# imwiser-esp-v01.net
KiCad netlist of a schematic drawn in EAGLE
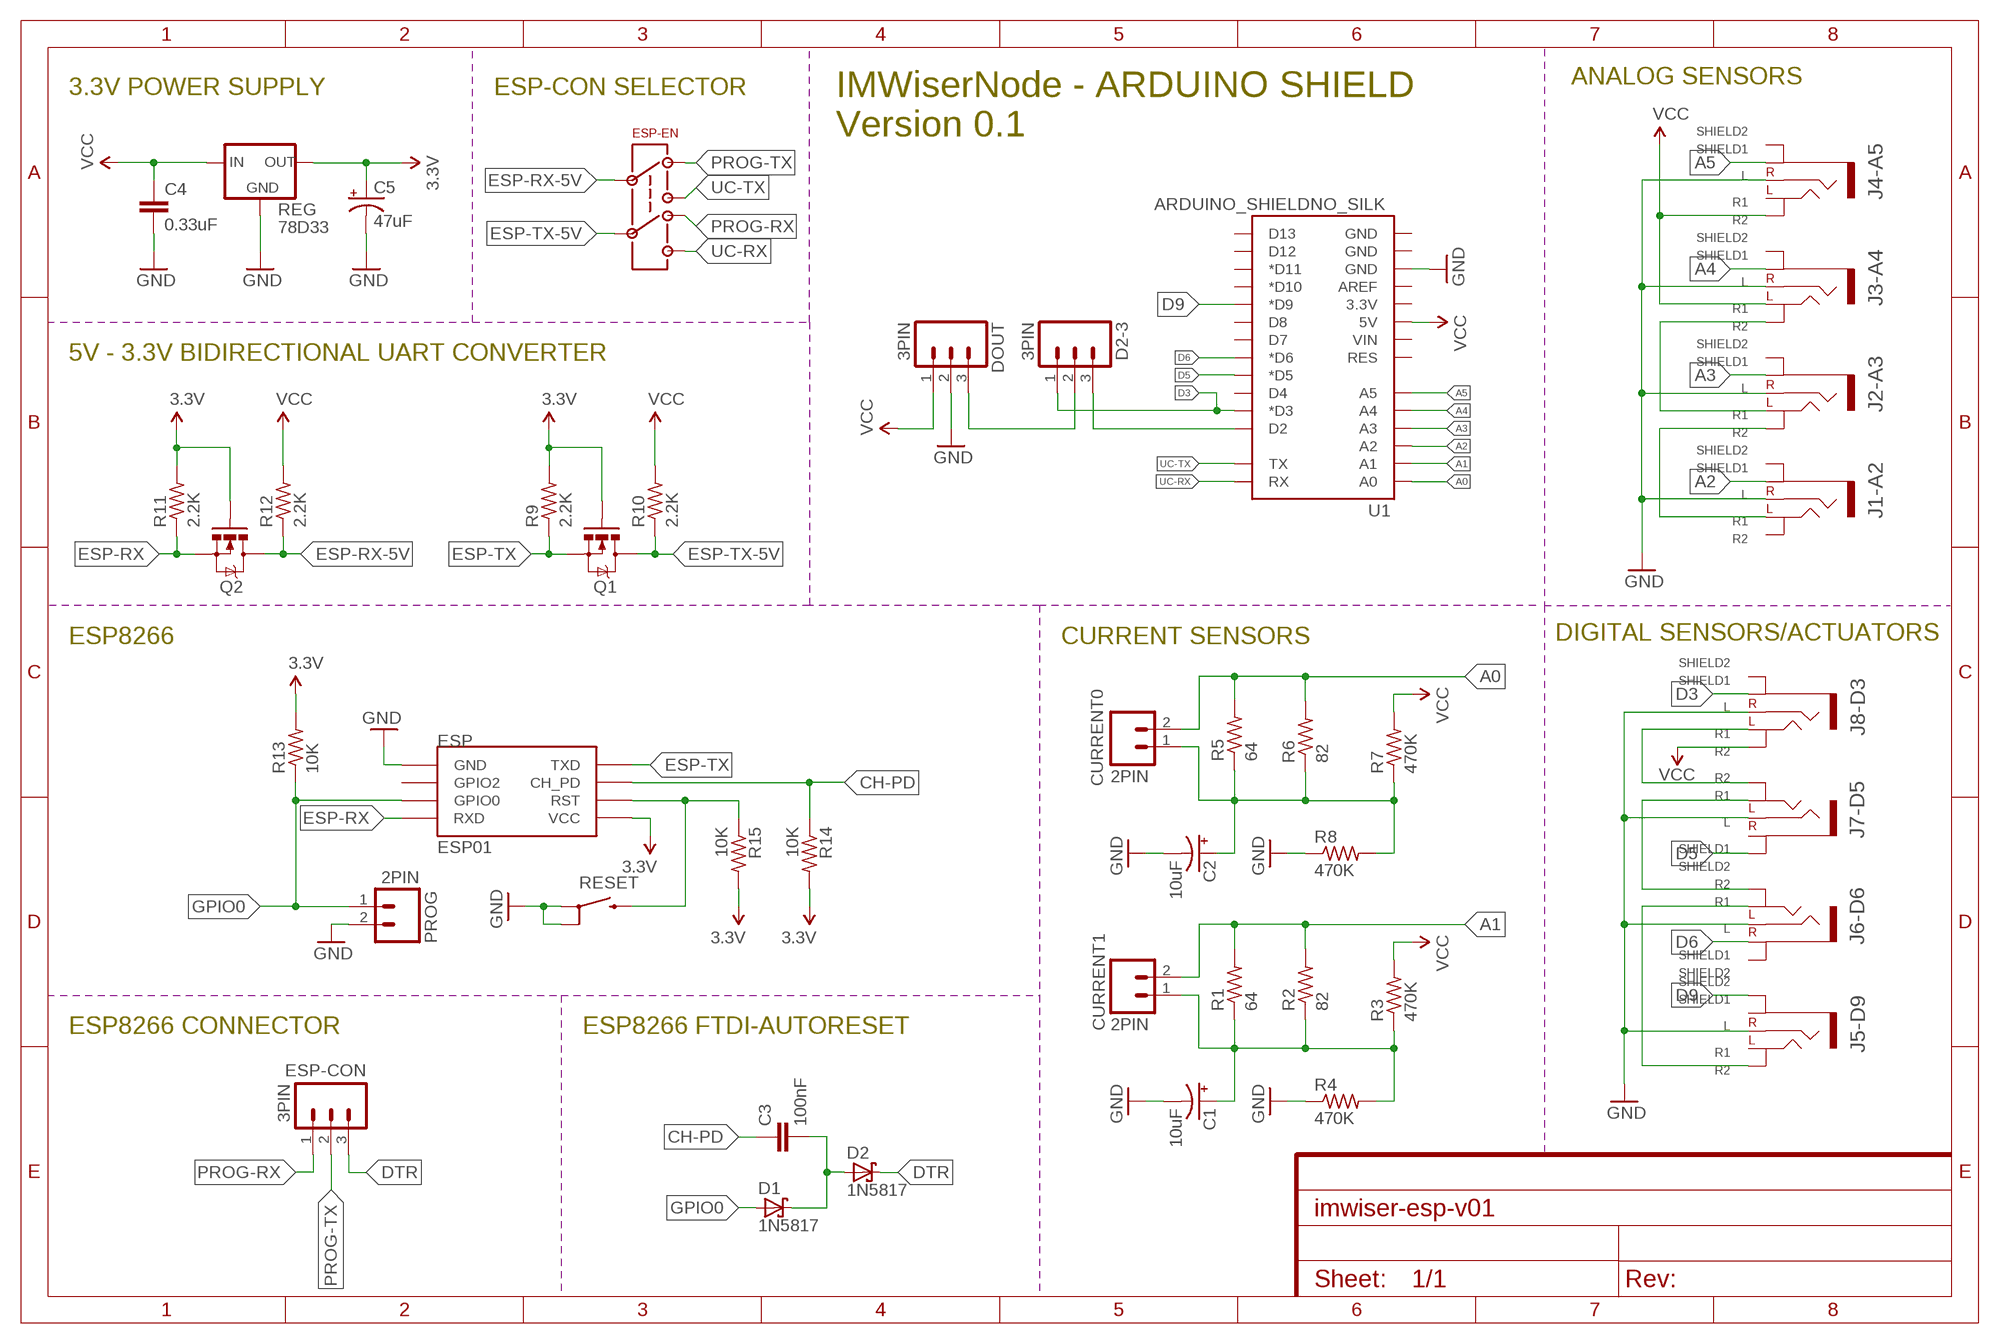
[diagram p0: schematic, sheet 1]

(export (version "E")
  (design (tool "Eeschema 10.0.6"))
  (components
    (comp (ref "C1")
      (value "10uF")
      (footprint "eagle-import:CPOL-RADIAL-10UF-25V")
      (libsource (lib "eagle-import") (part "10UF-25V-20%(PTH)"))
    )
    (comp (ref "C2")
      (value "10uF")
      (footprint "eagle-import:CPOL-RADIAL-10UF-25V")
      (libsource (lib "eagle-import") (part "10UF-25V-20%(PTH)"))
    )
    (comp (ref "C3")
      (value "100nF")
      (footprint "eagle-import:CAP-PTH-SMALL")
      (libsource (lib "eagle-import") (part "CAPPTH"))
    )
    (comp (ref "C4")
      (value "0.33uF")
      (footprint "eagle-import:CAP-PTH-SMALL")
      (libsource (lib "eagle-import") (part "CAPPTH"))
    )
    (comp (ref "C5")
      (value "47uF")
      (footprint "eagle-import:CPOL-RADIAL-10UF-25V")
      (libsource (lib "eagle-import") (part "10UF-25V-20%(PTH)"))
    )
    (comp (ref "CURRENT0")
      (value "2PIN")
      (footprint "eagle-import:1X02")
      (libsource (lib "eagle-import") (part "M02PTH"))
    )
    (comp (ref "CURRENT1")
      (value "2PIN")
      (footprint "eagle-import:1X02")
      (libsource (lib "eagle-import") (part "M02PTH"))
    )
    (comp (ref "D1")
      (value "1N5817")
      (footprint "eagle-import:DO41-7")
      (libsource (lib "eagle-import") (part "SCHOTTKY-DIODEDO41-7"))
    )
    (comp (ref "D2")
      (value "1N5817")
      (footprint "eagle-import:DO41-7")
      (libsource (lib "eagle-import") (part "SCHOTTKY-DIODEDO41-7"))
    )
    (comp (ref "D2-3")
      (value "3PIN")
      (footprint "eagle-import:1X03")
      (libsource (lib "eagle-import") (part "M03PTH"))
    )
    (comp (ref "DOUT")
      (value "3PIN")
      (footprint "eagle-import:1X03")
      (libsource (lib "eagle-import") (part "M03PTH"))
    )
    (comp (ref "ESP")
      (value "ESP01")
      (footprint "eagle-import:ESP01")
      (libsource (lib "eagle-import") (part "ESP01"))
    )
    (comp (ref "ESP-CON")
      (value "3PIN")
      (footprint "eagle-import:1X03")
      (libsource (lib "eagle-import") (part "M03PTH"))
    )
    (comp (ref "ESP-EN")
      (value "DPDT-GENERIC-SWITCH-7X7MM")
      (footprint "eagle-import:DPDT-PTH-7_7MM")
      (libsource (lib "eagle-import") (part "DPDT-GENERIC-SWITCH-7X7MM"))
    )
    (comp (ref "J1-A2")
      (value "PJ-313-SPAD")
      (footprint "eagle-import:PJ-313-5PIN-SMALL")
      (libsource (lib "eagle-import") (part "PJ-313-SPAD"))
    )
    (comp (ref "J2-A3")
      (value "PJ-313-SPAD")
      (footprint "eagle-import:PJ-313-5PIN-SMALL")
      (libsource (lib "eagle-import") (part "PJ-313-SPAD"))
    )
    (comp (ref "J3-A4")
      (value "PJ-313-SPAD")
      (footprint "eagle-import:PJ-313-5PIN-SMALL")
      (libsource (lib "eagle-import") (part "PJ-313-SPAD"))
    )
    (comp (ref "J4-A5")
      (value "PJ-313-SPAD")
      (footprint "eagle-import:PJ-313-5PIN-SMALL")
      (libsource (lib "eagle-import") (part "PJ-313-SPAD"))
    )
    (comp (ref "J5-D9")
      (value "PJ-313-SPAD")
      (footprint "eagle-import:PJ-313-5PIN-SMALL")
      (libsource (lib "eagle-import") (part "PJ-313-SPAD"))
    )
    (comp (ref "J6-D6")
      (value "PJ-313-SPAD")
      (footprint "eagle-import:PJ-313-5PIN-SMALL")
      (libsource (lib "eagle-import") (part "PJ-313-SPAD"))
    )
    (comp (ref "J7-D5")
      (value "PJ-313-SPAD")
      (footprint "eagle-import:PJ-313-5PIN-SMALL")
      (libsource (lib "eagle-import") (part "PJ-313-SPAD"))
    )
    (comp (ref "J8-D3")
      (value "PJ-313-SPAD")
      (footprint "eagle-import:PJ-313-5PIN-SMALL")
      (libsource (lib "eagle-import") (part "PJ-313-SPAD"))
    )
    (comp (ref "PROG")
      (value "2PIN")
      (footprint "eagle-import:1X02")
      (libsource (lib "eagle-import") (part "M02PTH"))
    )
    (comp (ref "Q1")
      (value "MOSFET-NCHANNEL2N7000")
      (footprint "eagle-import:TO-92")
      (libsource (lib "eagle-import") (part "MOSFET-NCHANNEL2N7000"))
    )
    (comp (ref "Q2")
      (value "MOSFET-NCHANNEL2N7000")
      (footprint "eagle-import:TO-92")
      (libsource (lib "eagle-import") (part "MOSFET-NCHANNEL2N7000"))
    )
    (comp (ref "R1")
      (value "64")
      (footprint "eagle-import:0207_10")
      (libsource (lib "eagle-import") (part "R-US_0207/10"))
    )
    (comp (ref "R2")
      (value "82")
      (footprint "eagle-import:0207_10")
      (libsource (lib "eagle-import") (part "R-US_0207/10"))
    )
    (comp (ref "R3")
      (value "470K")
      (footprint "eagle-import:0207_10")
      (libsource (lib "eagle-import") (part "R-US_0207/10"))
    )
    (comp (ref "R4")
      (value "470K")
      (footprint "eagle-import:0207_10")
      (libsource (lib "eagle-import") (part "R-US_0207/10"))
    )
    (comp (ref "R5")
      (value "64")
      (footprint "eagle-import:0207_10")
      (libsource (lib "eagle-import") (part "R-US_0207/10"))
    )
    (comp (ref "R6")
      (value "82")
      (footprint "eagle-import:0207_10")
      (libsource (lib "eagle-import") (part "R-US_0207/10"))
    )
    (comp (ref "R7")
      (value "470K")
      (footprint "eagle-import:0207_10")
      (libsource (lib "eagle-import") (part "R-US_0207/10"))
    )
    (comp (ref "R8")
      (value "470K")
      (footprint "eagle-import:0207_10")
      (libsource (lib "eagle-import") (part "R-US_0207/10"))
    )
    (comp (ref "R9")
      (value "2.2K")
      (footprint "eagle-import:0207_10")
      (libsource (lib "eagle-import") (part "R-US_0207/10"))
    )
    (comp (ref "R10")
      (value "2.2K")
      (footprint "eagle-import:0207_10")
      (libsource (lib "eagle-import") (part "R-US_0207/10"))
    )
    (comp (ref "R11")
      (value "2.2K")
      (footprint "eagle-import:0207_10")
      (libsource (lib "eagle-import") (part "R-US_0207/10"))
    )
    (comp (ref "R12")
      (value "2.2K")
      (footprint "eagle-import:0207_10")
      (libsource (lib "eagle-import") (part "R-US_0207/10"))
    )
    (comp (ref "R13")
      (value "10K")
      (footprint "eagle-import:0207_10")
      (libsource (lib "eagle-import") (part "R-US_0207/10"))
    )
    (comp (ref "R14")
      (value "10K")
      (footprint "eagle-import:0207_10")
      (libsource (lib "eagle-import") (part "R-US_0207/10"))
    )
    (comp (ref "R15")
      (value "10K")
      (footprint "eagle-import:0207_10")
      (libsource (lib "eagle-import") (part "R-US_0207/10"))
    )
    (comp (ref "REG")
      (value "78D33")
      (footprint "eagle-import:TO220-IGO")
      (libsource (lib "eagle-import") (part "V_REG_78XXSINK"))
    )
    (comp (ref "RESET")
      (value "SWITCH-MOMENTARY-2PTH")
      (footprint "eagle-import:TACTILE-PTH")
      (libsource (lib "eagle-import") (part "SWITCH-MOMENTARY-2PTH"))
    )
    (comp (ref "U1")
      (value "ARDUINO_SHIELDNO_SILK")
      (footprint "eagle-import:DUEMILANOVE_VIAS")
      (libsource (lib "eagle-import") (part "ARDUINO_SHIELDNO_SILK"))
    )
  )
  (nets
    (net (code "1") (name "3.3V") (class "Default")
      (node (ref "C5") (pin "1") (pinfunction "+_1") (pintype "passive"))
      (node (ref "ESP") (pin "VCC") (pinfunction "VCC_VCC") (pintype "bidirectional"))
      (node (ref "Q1") (pin "2") (pinfunction "G_2") (pintype "passive"))
      (node (ref "Q2") (pin "2") (pinfunction "G_2") (pintype "passive"))
      (node (ref "R11") (pin "2") (pinfunction "2_2") (pintype "passive"))
      (node (ref "R13") (pin "2") (pinfunction "2_2") (pintype "passive"))
      (node (ref "R14") (pin "2") (pinfunction "2_2") (pintype "passive"))
      (node (ref "R15") (pin "2") (pinfunction "2_2") (pintype "passive"))
      (node (ref "R9") (pin "2") (pinfunction "2_2") (pintype "passive"))
      (node (ref "REG") (pin "OUT") (pinfunction "OUT_OUT") (pintype "passive"))
    )
    (net (code "2") (name "A0") (class "Default")
      (node (ref "CURRENT0") (pin "2") (pinfunction "2_2") (pintype "passive"))
      (node (ref "R5") (pin "2") (pinfunction "2_2") (pintype "passive"))
      (node (ref "R6") (pin "2") (pinfunction "2_2") (pintype "passive"))
      (node (ref "U1") (pin "A0") (pinfunction "A0_A0") (pintype "bidirectional"))
    )
    (net (code "3") (name "A1") (class "Default")
      (node (ref "CURRENT1") (pin "2") (pinfunction "2_2") (pintype "passive"))
      (node (ref "R1") (pin "2") (pinfunction "2_2") (pintype "passive"))
      (node (ref "R2") (pin "2") (pinfunction "2_2") (pintype "passive"))
      (node (ref "U1") (pin "A1") (pinfunction "A1_A1") (pintype "bidirectional"))
    )
    (net (code "4") (name "A2") (class "Default")
      (node (ref "J1-A2") (pin "1.1") (pinfunction "SHIELD1_1.1") (pintype "bidirectional"))
      (node (ref "U1") (pin "A2") (pinfunction "A2_A2") (pintype "bidirectional"))
    )
    (net (code "5") (name "A3") (class "Default")
      (node (ref "J2-A3") (pin "1.1") (pinfunction "SHIELD1_1.1") (pintype "bidirectional"))
      (node (ref "U1") (pin "A3") (pinfunction "A3_A3") (pintype "bidirectional"))
    )
    (net (code "6") (name "A4") (class "Default")
      (node (ref "J3-A4") (pin "1.1") (pinfunction "SHIELD1_1.1") (pintype "bidirectional"))
      (node (ref "U1") (pin "A4") (pinfunction "A4_A4") (pintype "bidirectional"))
    )
    (net (code "7") (name "A5") (class "Default")
      (node (ref "J4-A5") (pin "1.1") (pinfunction "SHIELD1_1.1") (pintype "bidirectional"))
      (node (ref "U1") (pin "A5") (pinfunction "A5_A5") (pintype "bidirectional"))
    )
    (net (code "8") (name "CH-PD") (class "Default")
      (node (ref "C3") (pin "1") (pinfunction "1_1") (pintype "passive"))
      (node (ref "ESP") (pin "CH_PD") (pinfunction "CH_PD_CH_PD") (pintype "bidirectional"))
      (node (ref "R14") (pin "1") (pinfunction "1_1") (pintype "passive"))
    )
    (net (code "9") (name "D3") (class "Default")
      (node (ref "D2-3") (pin "1") (pinfunction "1_1") (pintype "passive"))
      (node (ref "J8-D3") (pin "1.1") (pinfunction "SHIELD1_1.1") (pintype "bidirectional"))
      (node (ref "U1") (pin "D3") (pinfunction "*D3_D3") (pintype "bidirectional"))
    )
    (net (code "10") (name "D5") (class "Default")
      (node (ref "J7-D5") (pin "1.2") (pinfunction "SHIELD2_1.2") (pintype "bidirectional"))
      (node (ref "U1") (pin "D5") (pinfunction "*D5_D5") (pintype "bidirectional"))
    )
    (net (code "11") (name "D6") (class "Default")
      (node (ref "J6-D6") (pin "1.1") (pinfunction "SHIELD1_1.1") (pintype "bidirectional"))
      (node (ref "U1") (pin "D6") (pinfunction "*D6_D6") (pintype "bidirectional"))
    )
    (net (code "12") (name "D9") (class "Default")
      (node (ref "J5-D9") (pin "1.2") (pinfunction "SHIELD2_1.2") (pintype "bidirectional"))
      (node (ref "U1") (pin "D9") (pinfunction "*D9_D9") (pintype "bidirectional"))
    )
    (net (code "13") (name "DTR") (class "Default")
      (node (ref "D2") (pin "C") (pinfunction "C_C") (pintype "passive"))
      (node (ref "ESP-CON") (pin "3") (pinfunction "3_3") (pintype "passive"))
    )
    (net (code "14") (name "ESP-RX") (class "Default")
      (node (ref "ESP") (pin "RX") (pinfunction "RXD_RX") (pintype "bidirectional"))
      (node (ref "Q2") (pin "1") (pinfunction "S_1") (pintype "passive"))
      (node (ref "R11") (pin "1") (pinfunction "1_1") (pintype "passive"))
    )
    (net (code "15") (name "ESP-RX-5V") (class "Default")
      (node (ref "ESP-EN") (pin "3-IN1") (pinfunction "IN1_3-IN1") (pintype "input"))
      (node (ref "Q2") (pin "3") (pinfunction "D_3") (pintype "passive"))
      (node (ref "R12") (pin "1") (pinfunction "1_1") (pintype "passive"))
    )
    (net (code "16") (name "ESP-TX") (class "Default")
      (node (ref "ESP") (pin "TX") (pinfunction "TXD_TX") (pintype "bidirectional"))
      (node (ref "Q1") (pin "1") (pinfunction "S_1") (pintype "passive"))
      (node (ref "R9") (pin "1") (pinfunction "1_1") (pintype "passive"))
    )
    (net (code "17") (name "ESP-TX-5V") (class "Default")
      (node (ref "ESP-EN") (pin "4-IN2") (pinfunction "IN2_4-IN2") (pintype "input"))
      (node (ref "Q1") (pin "3") (pinfunction "D_3") (pintype "passive"))
      (node (ref "R10") (pin "1") (pinfunction "1_1") (pintype "passive"))
    )
    (net (code "18") (name "GND") (class "Default")
      (node (ref "C1") (pin "2") (pinfunction "-_2") (pintype "passive"))
      (node (ref "C2") (pin "2") (pinfunction "-_2") (pintype "passive"))
      (node (ref "C4") (pin "2") (pinfunction "2_2") (pintype "passive"))
      (node (ref "C5") (pin "2") (pinfunction "-_2") (pintype "passive"))
      (node (ref "DOUT") (pin "2") (pinfunction "2_2") (pintype "passive"))
      (node (ref "ESP") (pin "GND") (pinfunction "GND_GND") (pintype "bidirectional"))
      (node (ref "J1-A2") (pin "2") (pinfunction "R_2") (pintype "bidirectional"))
      (node (ref "J2-A3") (pin "2") (pinfunction "R_2") (pintype "bidirectional"))
      (node (ref "J3-A4") (pin "2") (pinfunction "R_2") (pintype "bidirectional"))
      (node (ref "J4-A5") (pin "2") (pinfunction "R_2") (pintype "bidirectional"))
      (node (ref "J5-D9") (pin "2") (pinfunction "R_2") (pintype "bidirectional"))
      (node (ref "J6-D6") (pin "2") (pinfunction "R_2") (pintype "bidirectional"))
      (node (ref "J7-D5") (pin "2") (pinfunction "R_2") (pintype "bidirectional"))
      (node (ref "J8-D3") (pin "2") (pinfunction "R_2") (pintype "bidirectional"))
      (node (ref "PROG") (pin "2") (pinfunction "2_2") (pintype "passive"))
      (node (ref "R4") (pin "1") (pinfunction "1_1") (pintype "passive"))
      (node (ref "R8") (pin "1") (pinfunction "1_1") (pintype "passive"))
      (node (ref "REG") (pin "GND") (pinfunction "GND_GND") (pintype "input"))
      (node (ref "RESET") (pin "1") (pinfunction "1_1") (pintype "passive"))
      (node (ref "RESET") (pin "2") (pinfunction "P$1_2") (pintype "passive"))
      (node (ref "U1") (pin "GND@2") (pinfunction "GND_GND@2") (pintype "bidirectional"))
    )
    (net (code "19") (name "GPIO0") (class "Default")
      (node (ref "D1") (pin "A") (pinfunction "A_A") (pintype "passive"))
      (node (ref "ESP") (pin "GPIO0") (pinfunction "GPIO0_GPIO0") (pintype "bidirectional"))
      (node (ref "PROG") (pin "1") (pinfunction "1_1") (pintype "passive"))
      (node (ref "R13") (pin "1") (pinfunction "1_1") (pintype "passive"))
    )
    (net (code "20") (name "Net-(C1-+)") (class "Default")
      (node (ref "C1") (pin "1") (pinfunction "+_1") (pintype "passive"))
      (node (ref "CURRENT1") (pin "1") (pinfunction "1_1") (pintype "passive"))
      (node (ref "R1") (pin "1") (pinfunction "1_1") (pintype "passive"))
      (node (ref "R2") (pin "1") (pinfunction "1_1") (pintype "passive"))
      (node (ref "R3") (pin "1") (pinfunction "1_1") (pintype "passive"))
      (node (ref "R4") (pin "2") (pinfunction "2_2") (pintype "passive"))
    )
    (net (code "21") (name "Net-(C2-+)") (class "Default")
      (node (ref "C2") (pin "1") (pinfunction "+_1") (pintype "passive"))
      (node (ref "CURRENT0") (pin "1") (pinfunction "1_1") (pintype "passive"))
      (node (ref "R5") (pin "1") (pinfunction "1_1") (pintype "passive"))
      (node (ref "R6") (pin "1") (pinfunction "1_1") (pintype "passive"))
      (node (ref "R7") (pin "1") (pinfunction "1_1") (pintype "passive"))
      (node (ref "R8") (pin "2") (pinfunction "2_2") (pintype "passive"))
    )
    (net (code "22") (name "Net-(C3-Pad2)") (class "Default")
      (node (ref "C3") (pin "2") (pinfunction "2_2") (pintype "passive"))
      (node (ref "D1") (pin "C") (pinfunction "C_C") (pintype "passive"))
      (node (ref "D2") (pin "A") (pinfunction "A_A") (pintype "passive"))
    )
    (net (code "23") (name "Net-(D2-3-Pad2)") (class "Default")
      (node (ref "D2-3") (pin "2") (pinfunction "2_2") (pintype "passive"))
      (node (ref "DOUT") (pin "3") (pinfunction "3_3") (pintype "passive"))
    )
    (net (code "24") (name "Net-(D2-3-Pad3)") (class "Default")
      (node (ref "D2-3") (pin "3") (pinfunction "3_3") (pintype "passive"))
      (node (ref "U1") (pin "D2") (pinfunction "D2_D2") (pintype "bidirectional"))
    )
    (net (code "25") (name "Net-(J1-A2-L1)") (class "Default")
      (node (ref "J1-A2") (pin "3.1") (pinfunction "L1_3.1") (pintype "bidirectional"))
      (node (ref "J2-A3") (pin "3.2") (pinfunction "L2_3.2") (pintype "bidirectional"))
    )
    (net (code "26") (name "Net-(J2-A3-L1)") (class "Default")
      (node (ref "J2-A3") (pin "3.1") (pinfunction "L1_3.1") (pintype "bidirectional"))
      (node (ref "J3-A4") (pin "3.2") (pinfunction "L2_3.2") (pintype "bidirectional"))
    )
    (net (code "27") (name "Net-(J5-D9-L2)") (class "Default")
      (node (ref "J5-D9") (pin "3.2") (pinfunction "L2_3.2") (pintype "bidirectional"))
      (node (ref "J6-D6") (pin "3.1") (pinfunction "L1_3.1") (pintype "bidirectional"))
    )
    (net (code "28") (name "Net-(J6-D6-L2)") (class "Default")
      (node (ref "J6-D6") (pin "3.2") (pinfunction "L2_3.2") (pintype "bidirectional"))
      (node (ref "J7-D5") (pin "3.1") (pinfunction "L1_3.1") (pintype "bidirectional"))
    )
    (net (code "29") (name "Net-(J7-D5-L2)") (class "Default")
      (node (ref "J7-D5") (pin "3.2") (pinfunction "L2_3.2") (pintype "bidirectional"))
      (node (ref "J8-D3") (pin "3.1") (pinfunction "L1_3.1") (pintype "bidirectional"))
    )
    (net (code "30") (name "Net-(RESET-2)") (class "Default")
      (node (ref "ESP") (pin "RST") (pinfunction "RST_RST") (pintype "bidirectional"))
      (node (ref "R15") (pin "1") (pinfunction "1_1") (pintype "passive"))
      (node (ref "RESET") (pin "3") (pinfunction "2_3") (pintype "passive"))
    )
    (net (code "31") (name "PROG-RX") (class "Default")
      (node (ref "ESP-CON") (pin "1") (pinfunction "1_1") (pintype "passive"))
      (node (ref "ESP-EN") (pin "2-OUT2-A") (pinfunction "OUT2-A_2-OUT2-A") (pintype "output"))
    )
    (net (code "32") (name "PROG-TX") (class "Default")
      (node (ref "ESP-CON") (pin "2") (pinfunction "2_2") (pintype "passive"))
      (node (ref "ESP-EN") (pin "1-OUT1-A") (pinfunction "OUT1-A_1-OUT1-A") (pintype "output"))
    )
    (net (code "33") (name "UC-RX") (class "Default")
      (node (ref "ESP-EN") (pin "6-OUT2-B") (pinfunction "OUT2-B_6-OUT2-B") (pintype "output"))
      (node (ref "U1") (pin "RX") (pinfunction "RX_RX") (pintype "bidirectional"))
    )
    (net (code "34") (name "UC-TX") (class "Default")
      (node (ref "ESP-EN") (pin "5-OUT1-B") (pinfunction "OUT1-B_5-OUT1-B") (pintype "output"))
      (node (ref "U1") (pin "TX") (pinfunction "TX_TX") (pintype "bidirectional"))
    )
    (net (code "35") (name "VCC") (class "Default")
      (node (ref "C4") (pin "1") (pinfunction "1_1") (pintype "passive"))
      (node (ref "DOUT") (pin "1") (pinfunction "1_1") (pintype "passive"))
      (node (ref "J3-A4") (pin "3.1") (pinfunction "L1_3.1") (pintype "bidirectional"))
      (node (ref "J4-A5") (pin "3.2") (pinfunction "L2_3.2") (pintype "bidirectional"))
      (node (ref "J8-D3") (pin "3.2") (pinfunction "L2_3.2") (pintype "bidirectional"))
      (node (ref "R10") (pin "2") (pinfunction "2_2") (pintype "passive"))
      (node (ref "R12") (pin "2") (pinfunction "2_2") (pintype "passive"))
      (node (ref "R3") (pin "2") (pinfunction "2_2") (pintype "passive"))
      (node (ref "R7") (pin "2") (pinfunction "2_2") (pintype "passive"))
      (node (ref "REG") (pin "IN") (pinfunction "IN_IN") (pintype "input"))
      (node (ref "U1") (pin "5V") (pinfunction "5V_5V") (pintype "bidirectional"))
    )
    (net (code "36") (name "unconnected-(ESP-PadGPIO2)") (class "Default")
      (node (ref "ESP") (pin "GPIO2") (pinfunction "GPIO2_GPIO2") (pintype "bidirectional"))
    )
    (net (code "37") (name "unconnected-(J1-A2-L2-Pad3.2)") (class "Default")
      (node (ref "J1-A2") (pin "3.2") (pinfunction "L2_3.2") (pintype "bidirectional"))
    )
    (net (code "38") (name "unconnected-(J1-A2-SHIELD2-Pad1.2)") (class "Default")
      (node (ref "J1-A2") (pin "1.2") (pinfunction "SHIELD2_1.2") (pintype "bidirectional"))
    )
    (net (code "39") (name "unconnected-(J2-A3-SHIELD2-Pad1.2)") (class "Default")
      (node (ref "J2-A3") (pin "1.2") (pinfunction "SHIELD2_1.2") (pintype "bidirectional"))
    )
    (net (code "40") (name "unconnected-(J3-A4-SHIELD2-Pad1.2)") (class "Default")
      (node (ref "J3-A4") (pin "1.2") (pinfunction "SHIELD2_1.2") (pintype "bidirectional"))
    )
    (net (code "41") (name "unconnected-(J4-A5-L1-Pad3.1)") (class "Default")
      (node (ref "J4-A5") (pin "3.1") (pinfunction "L1_3.1") (pintype "bidirectional"))
    )
    (net (code "42") (name "unconnected-(J4-A5-SHIELD2-Pad1.2)") (class "Default")
      (node (ref "J4-A5") (pin "1.2") (pinfunction "SHIELD2_1.2") (pintype "bidirectional"))
    )
    (net (code "43") (name "unconnected-(J5-D9-L1-Pad3.1)") (class "Default")
      (node (ref "J5-D9") (pin "3.1") (pinfunction "L1_3.1") (pintype "bidirectional"))
    )
    (net (code "44") (name "unconnected-(J5-D9-SHIELD1-Pad1.1)") (class "Default")
      (node (ref "J5-D9") (pin "1.1") (pinfunction "SHIELD1_1.1") (pintype "bidirectional"))
    )
    (net (code "45") (name "unconnected-(J6-D6-SHIELD2-Pad1.2)") (class "Default")
      (node (ref "J6-D6") (pin "1.2") (pinfunction "SHIELD2_1.2") (pintype "bidirectional"))
    )
    (net (code "46") (name "unconnected-(J7-D5-SHIELD1-Pad1.1)") (class "Default")
      (node (ref "J7-D5") (pin "1.1") (pinfunction "SHIELD1_1.1") (pintype "bidirectional"))
    )
    (net (code "47") (name "unconnected-(J8-D3-SHIELD2-Pad1.2)") (class "Default")
      (node (ref "J8-D3") (pin "1.2") (pinfunction "SHIELD2_1.2") (pintype "bidirectional"))
    )
    (net (code "48") (name "unconnected-(U1-*D10-PadD10)") (class "Default")
      (node (ref "U1") (pin "D10") (pinfunction "*D10_D10") (pintype "bidirectional"))
    )
    (net (code "49") (name "unconnected-(U1-*D11-PadD11)") (class "Default")
      (node (ref "U1") (pin "D11") (pinfunction "*D11_D11") (pintype "bidirectional"))
    )
    (net (code "50") (name "unconnected-(U1-GND-PadGND@0)") (class "Default")
      (node (ref "U1") (pin "GND@0") (pinfunction "GND_GND@0") (pintype "bidirectional"))
    )
    (net (code "51") (name "unconnected-(U1-GND-PadGND@1)") (class "Default")
      (node (ref "U1") (pin "GND@1") (pinfunction "GND_GND@1") (pintype "bidirectional"))
    )
    (net (code "52") (name "unconnected-(U1-Pad3.3V)") (class "Default")
      (node (ref "U1") (pin "3.3V") (pinfunction "3.3V_3.3V") (pintype "bidirectional"))
    )
    (net (code "53") (name "unconnected-(U1-PadAREF)") (class "Default")
      (node (ref "U1") (pin "AREF") (pinfunction "AREF_AREF") (pintype "bidirectional"))
    )
    (net (code "54") (name "unconnected-(U1-PadD4)") (class "Default")
      (node (ref "U1") (pin "D4") (pinfunction "D4_D4") (pintype "bidirectional"))
    )
    (net (code "55") (name "unconnected-(U1-PadD7)") (class "Default")
      (node (ref "U1") (pin "D7") (pinfunction "D7_D7") (pintype "bidirectional"))
    )
    (net (code "56") (name "unconnected-(U1-PadD8)") (class "Default")
      (node (ref "U1") (pin "D8") (pinfunction "D8_D8") (pintype "bidirectional"))
    )
    (net (code "57") (name "unconnected-(U1-PadD12)") (class "Default")
      (node (ref "U1") (pin "D12") (pinfunction "D12_D12") (pintype "bidirectional"))
    )
    (net (code "58") (name "unconnected-(U1-PadD13)") (class "Default")
      (node (ref "U1") (pin "D13") (pinfunction "D13_D13") (pintype "bidirectional"))
    )
    (net (code "59") (name "unconnected-(U1-PadRES)") (class "Default")
      (node (ref "U1") (pin "RES") (pinfunction "RES_RES") (pintype "bidirectional"))
    )
    (net (code "60") (name "unconnected-(U1-PadVIN)") (class "Default")
      (node (ref "U1") (pin "VIN") (pinfunction "VIN_VIN") (pintype "bidirectional"))
    )
  )
)
